# shield-p1000_v53.net
KiCad netlist of a schematic drawn in EAGLE
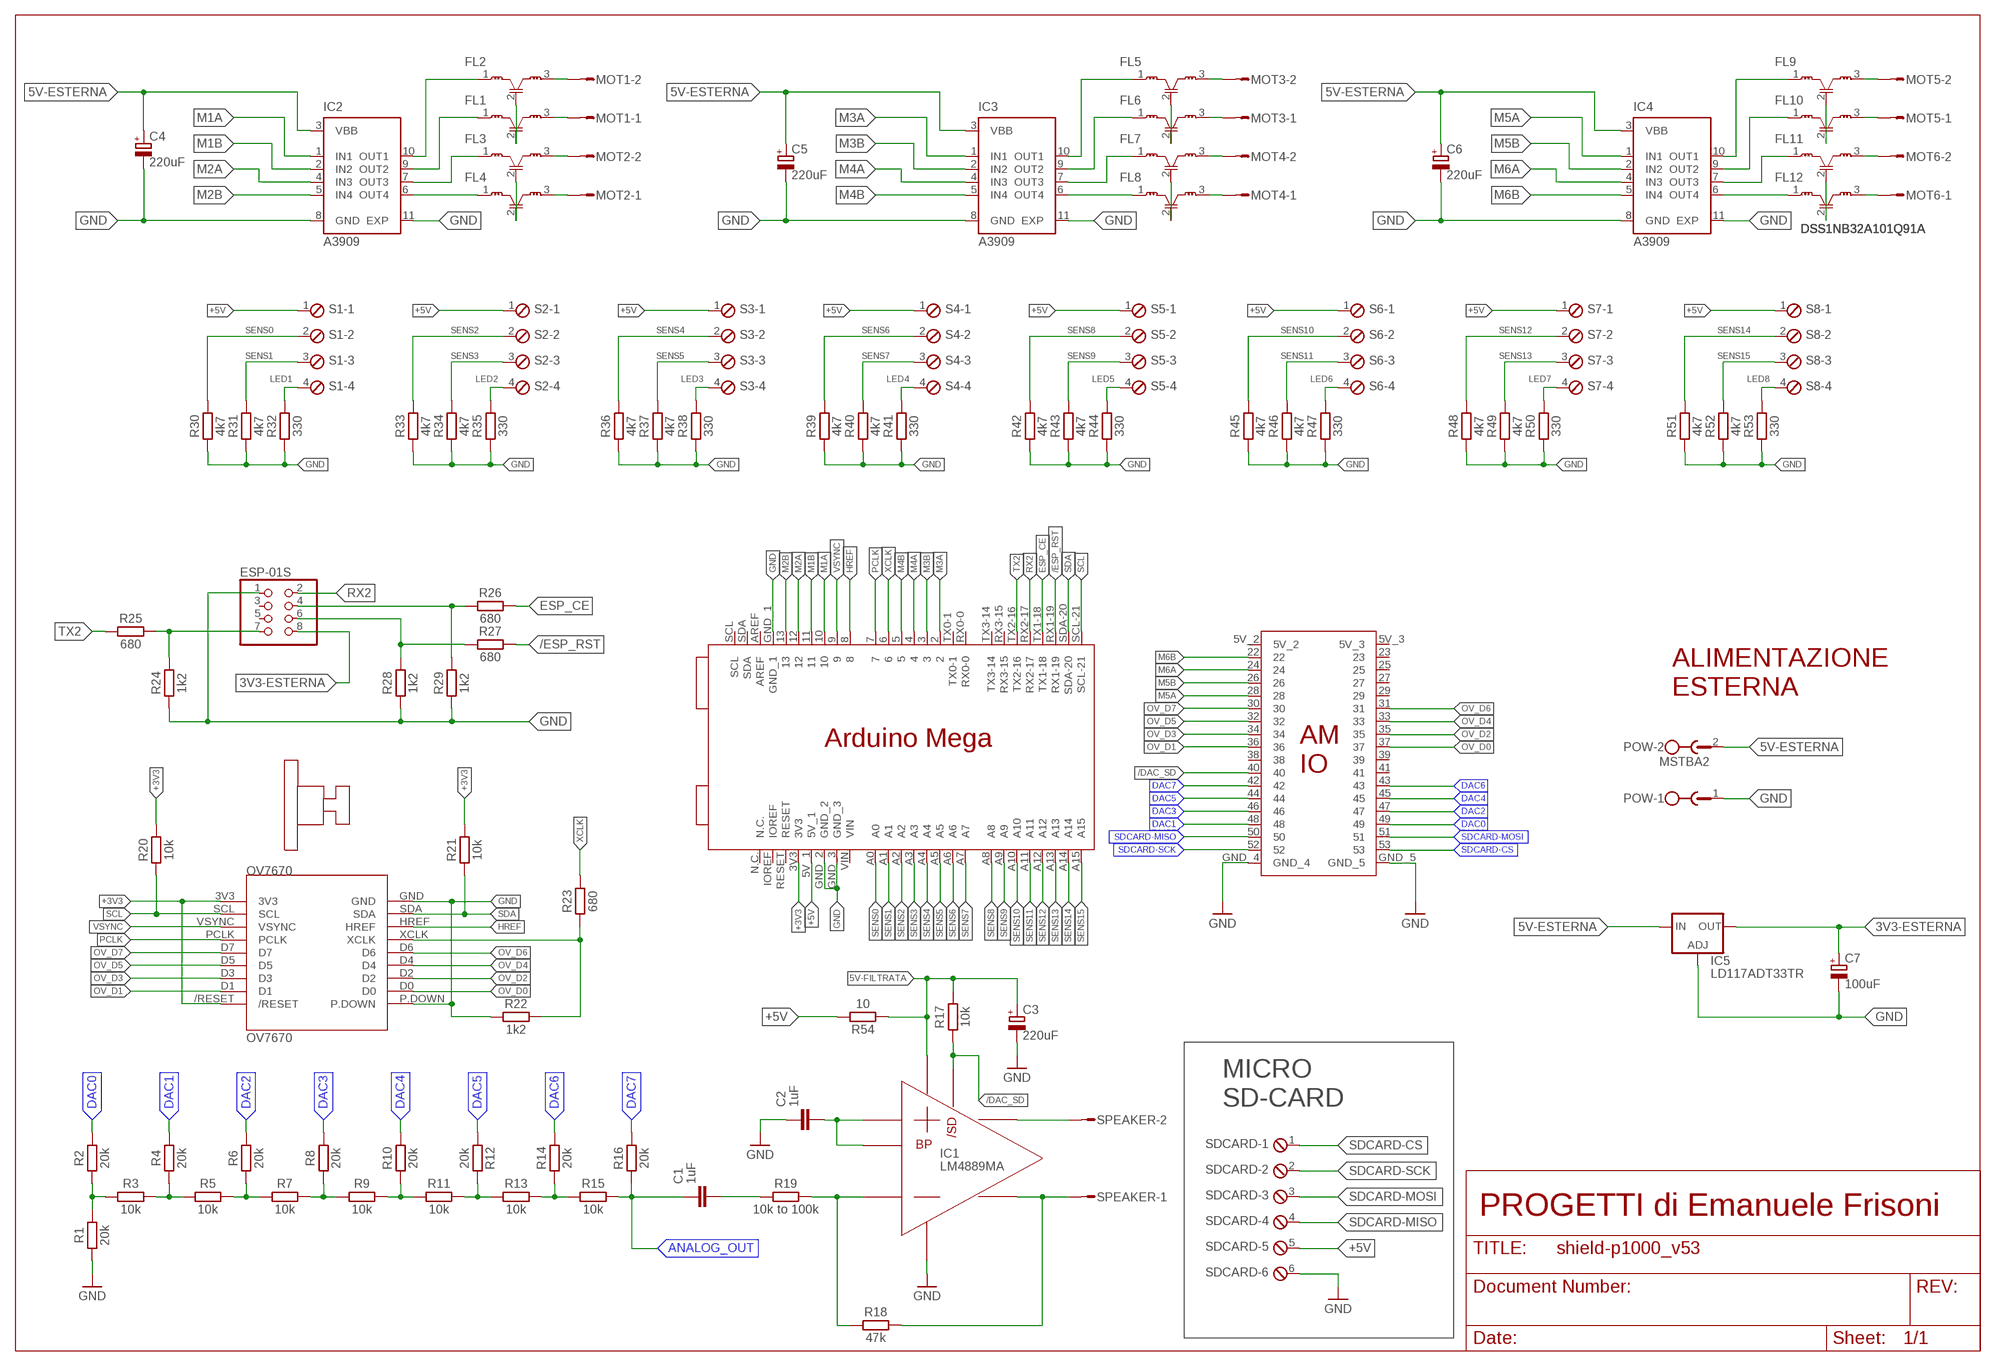
[diagram p0: schematic, sheet 1]

(export (version "E")
  (design (tool "Eeschema 10.0.6"))
  (components
    (comp (ref "ARDUINO-MEGA1")
      (value "ARDUINO-MEGA-SH")
      (footprint "eagle-import:ARDUINO-MEGA-SH")
      (libsource (lib "eagle-import") (part "ARDUINO-MEGA-SH"))
    )
    (comp (ref "C1")
      (value "1uF")
      (footprint "eagle-import:CAPC1608X85")
      (libsource (lib "eagle-import") (part "CCHIP-0603(1608-METRIC)_"))
    )
    (comp (ref "C2")
      (value "1uF")
      (footprint "eagle-import:CAPC1608X85")
      (libsource (lib "eagle-import") (part "CCHIP-0603(1608-METRIC)_"))
    )
    (comp (ref "C3")
      (value "220uF")
      (footprint "eagle-import:E3,5-10")
      (libsource (lib "eagle-import") (part "CPOL-EUE3.5-10"))
    )
    (comp (ref "C4")
      (value "220uF")
      (footprint "eagle-import:E3,5-10")
      (libsource (lib "eagle-import") (part "CPOL-EUE3.5-10"))
    )
    (comp (ref "C5")
      (value "220uF")
      (footprint "eagle-import:E3,5-10")
      (libsource (lib "eagle-import") (part "CPOL-EUE3.5-10"))
    )
    (comp (ref "C6")
      (value "220uF")
      (footprint "eagle-import:E3,5-10")
      (libsource (lib "eagle-import") (part "CPOL-EUE3.5-10"))
    )
    (comp (ref "C7")
      (value "100uF")
      (footprint "eagle-import:E3,5-10")
      (libsource (lib "eagle-import") (part "CPOL-EUE3.5-10"))
    )
    (comp (ref "ESP-01S")
      (value "PINHD-2X4")
      (footprint "eagle-import:2X04")
      (libsource (lib "eagle-import") (part "PINHD-2X4"))
    )
    (comp (ref "FL1")
      (value "DSS1NB32A101Q91A")
      (footprint "eagle-import:RADIAL-3")
      (fields (field (name "MANUFACTURER") "Murata Electronics") (field (name "CREATED_BY") "PCBLayout.com"))
      (libsource (lib "eagle-import") (part "DSS1NB32A101Q91A"))
    )
    (comp (ref "FL2")
      (value "DSS1NB32A101Q91A")
      (footprint "eagle-import:RADIAL-3")
      (fields (field (name "MANUFACTURER") "Murata Electronics") (field (name "CREATED_BY") "PCBLayout.com"))
      (libsource (lib "eagle-import") (part "DSS1NB32A101Q91A"))
    )
    (comp (ref "FL3")
      (value "DSS1NB32A101Q91A")
      (footprint "eagle-import:RADIAL-3")
      (fields (field (name "MANUFACTURER") "Murata Electronics") (field (name "CREATED_BY") "PCBLayout.com"))
      (libsource (lib "eagle-import") (part "DSS1NB32A101Q91A"))
    )
    (comp (ref "FL4")
      (value "DSS1NB32A101Q91A")
      (footprint "eagle-import:RADIAL-3")
      (fields (field (name "MANUFACTURER") "Murata Electronics") (field (name "CREATED_BY") "PCBLayout.com"))
      (libsource (lib "eagle-import") (part "DSS1NB32A101Q91A"))
    )
    (comp (ref "FL5")
      (value "DSS1NB32A101Q91A")
      (footprint "eagle-import:RADIAL-3")
      (fields (field (name "MANUFACTURER") "Murata Electronics") (field (name "CREATED_BY") "PCBLayout.com"))
      (libsource (lib "eagle-import") (part "DSS1NB32A101Q91A"))
    )
    (comp (ref "FL6")
      (value "DSS1NB32A101Q91A")
      (footprint "eagle-import:RADIAL-3")
      (fields (field (name "MANUFACTURER") "Murata Electronics") (field (name "CREATED_BY") "PCBLayout.com"))
      (libsource (lib "eagle-import") (part "DSS1NB32A101Q91A"))
    )
    (comp (ref "FL7")
      (value "DSS1NB32A101Q91A")
      (footprint "eagle-import:RADIAL-3")
      (fields (field (name "MANUFACTURER") "Murata Electronics") (field (name "CREATED_BY") "PCBLayout.com"))
      (libsource (lib "eagle-import") (part "DSS1NB32A101Q91A"))
    )
    (comp (ref "FL8")
      (value "DSS1NB32A101Q91A")
      (footprint "eagle-import:RADIAL-3")
      (fields (field (name "MANUFACTURER") "Murata Electronics") (field (name "CREATED_BY") "PCBLayout.com"))
      (libsource (lib "eagle-import") (part "DSS1NB32A101Q91A"))
    )
    (comp (ref "FL9")
      (value "DSS1NB32A101Q91A")
      (footprint "eagle-import:RADIAL-3")
      (fields (field (name "MANUFACTURER") "Murata Electronics") (field (name "CREATED_BY") "PCBLayout.com"))
      (libsource (lib "eagle-import") (part "DSS1NB32A101Q91A"))
    )
    (comp (ref "FL10")
      (value "DSS1NB32A101Q91A")
      (footprint "eagle-import:RADIAL-3")
      (fields (field (name "MANUFACTURER") "Murata Electronics") (field (name "CREATED_BY") "PCBLayout.com"))
      (libsource (lib "eagle-import") (part "DSS1NB32A101Q91A"))
    )
    (comp (ref "FL11")
      (value "DSS1NB32A101Q91A")
      (footprint "eagle-import:RADIAL-3")
      (fields (field (name "MANUFACTURER") "Murata Electronics") (field (name "CREATED_BY") "PCBLayout.com"))
      (libsource (lib "eagle-import") (part "DSS1NB32A101Q91A"))
    )
    (comp (ref "FL12")
      (value "DSS1NB32A101Q91A")
      (footprint "eagle-import:RADIAL-3")
      (fields (field (name "MANUFACTURER") "Murata Electronics") (field (name "CREATED_BY") "PCBLayout.com"))
      (libsource (lib "eagle-import") (part "DSS1NB32A101Q91A"))
    )
    (comp (ref "IC1")
      (value "LM4889MA")
      (footprint "eagle-import:SOIC127P599X175-8N")
      (libsource (lib "eagle-import") (part "LM4889MA"))
    )
    (comp (ref "IC2")
      (value "A3909")
      (footprint "eagle-import:10-MSOP")
      (libsource (lib "eagle-import") (part "A3909LY"))
    )
    (comp (ref "IC3")
      (value "A3909")
      (footprint "eagle-import:10-MSOP")
      (libsource (lib "eagle-import") (part "A3909LY"))
    )
    (comp (ref "IC4")
      (value "A3909")
      (footprint "eagle-import:10-MSOP")
      (libsource (lib "eagle-import") (part "A3909LY"))
    )
    (comp (ref "IC5")
      (value "LD117ADT33TR")
      (footprint "eagle-import:DPACK")
      (libsource (lib "eagle-import") (part "LD117A?DT33TR"))
    )
    (comp (ref "MOT1")
      (value "S02P")
      (footprint "eagle-import:S02P")
      (libsource (lib "eagle-import") (part "S02P"))
    )
    (comp (ref "MOT2")
      (value "S02P")
      (footprint "eagle-import:S02P")
      (libsource (lib "eagle-import") (part "S02P"))
    )
    (comp (ref "MOT3")
      (value "S02P")
      (footprint "eagle-import:S02P")
      (libsource (lib "eagle-import") (part "S02P"))
    )
    (comp (ref "MOT4")
      (value "S02P")
      (footprint "eagle-import:S02P")
      (libsource (lib "eagle-import") (part "S02P"))
    )
    (comp (ref "MOT5")
      (value "S02P")
      (footprint "eagle-import:S02P")
      (libsource (lib "eagle-import") (part "S02P"))
    )
    (comp (ref "MOT6")
      (value "S02P")
      (footprint "eagle-import:S02P")
      (libsource (lib "eagle-import") (part "S02P"))
    )
    (comp (ref "OV7670")
      (value "OV7670")
      (footprint "eagle-import:OV7670-HEADER")
      (libsource (lib "eagle-import") (part "OV7670"))
    )
    (comp (ref "POW")
      (value "MSTBA2")
      (footprint "eagle-import:MSTBA2")
      (fields (field (name "MF") "FARNELL") (field (name "MPN") "1757242"))
      (libsource (lib "eagle-import") (part "MSTBA2"))
    )
    (comp (ref "R1")
      (value "20k")
      (footprint "eagle-import:RESC1608X60")
      (libsource (lib "eagle-import") (part "RCHIP-0603(1608-METRIC)_"))
    )
    (comp (ref "R2")
      (value "20k")
      (footprint "eagle-import:RESC1608X60")
      (libsource (lib "eagle-import") (part "RCHIP-0603(1608-METRIC)_"))
    )
    (comp (ref "R3")
      (value "10k")
      (footprint "eagle-import:RESC1608X60")
      (libsource (lib "eagle-import") (part "RCHIP-0603(1608-METRIC)_"))
    )
    (comp (ref "R4")
      (value "20k")
      (footprint "eagle-import:RESC1608X60")
      (libsource (lib "eagle-import") (part "RCHIP-0603(1608-METRIC)_"))
    )
    (comp (ref "R5")
      (value "10k")
      (footprint "eagle-import:RESC1608X60")
      (libsource (lib "eagle-import") (part "RCHIP-0603(1608-METRIC)_"))
    )
    (comp (ref "R6")
      (value "20k")
      (footprint "eagle-import:RESC1608X60")
      (libsource (lib "eagle-import") (part "RCHIP-0603(1608-METRIC)_"))
    )
    (comp (ref "R7")
      (value "10k")
      (footprint "eagle-import:RESC1608X60")
      (libsource (lib "eagle-import") (part "RCHIP-0603(1608-METRIC)_"))
    )
    (comp (ref "R8")
      (value "20k")
      (footprint "eagle-import:RESC1608X60")
      (libsource (lib "eagle-import") (part "RCHIP-0603(1608-METRIC)_"))
    )
    (comp (ref "R9")
      (value "10k")
      (footprint "eagle-import:RESC1608X60")
      (libsource (lib "eagle-import") (part "RCHIP-0603(1608-METRIC)_"))
    )
    (comp (ref "R10")
      (value "20k")
      (footprint "eagle-import:RESC1608X60")
      (libsource (lib "eagle-import") (part "RCHIP-0603(1608-METRIC)_"))
    )
    (comp (ref "R11")
      (value "10k")
      (footprint "eagle-import:RESC1608X60")
      (libsource (lib "eagle-import") (part "RCHIP-0603(1608-METRIC)_"))
    )
    (comp (ref "R12")
      (value "20k")
      (footprint "eagle-import:RESC1608X60")
      (libsource (lib "eagle-import") (part "RCHIP-0603(1608-METRIC)_"))
    )
    (comp (ref "R13")
      (value "10k")
      (footprint "eagle-import:RESC1608X60")
      (libsource (lib "eagle-import") (part "RCHIP-0603(1608-METRIC)_"))
    )
    (comp (ref "R14")
      (value "20k")
      (footprint "eagle-import:RESC1608X60")
      (libsource (lib "eagle-import") (part "RCHIP-0603(1608-METRIC)_"))
    )
    (comp (ref "R15")
      (value "10k")
      (footprint "eagle-import:RESC1608X60")
      (libsource (lib "eagle-import") (part "RCHIP-0603(1608-METRIC)_"))
    )
    (comp (ref "R16")
      (value "20k")
      (footprint "eagle-import:RESC1608X60")
      (libsource (lib "eagle-import") (part "RCHIP-0603(1608-METRIC)_"))
    )
    (comp (ref "R17")
      (value "10k")
      (footprint "eagle-import:RESC1608X60")
      (libsource (lib "eagle-import") (part "RCHIP-0603(1608-METRIC)_"))
    )
    (comp (ref "R18")
      (value "47k")
      (footprint "eagle-import:RESC1608X60")
      (libsource (lib "eagle-import") (part "RCHIP-0603(1608-METRIC)_"))
    )
    (comp (ref "R19")
      (value "10k to 100k")
      (footprint "eagle-import:RESAD724W46L381D178B")
      (libsource (lib "eagle-import") (part "RAXIAL-7.2MM-PITCH_"))
    )
    (comp (ref "R20")
      (value "10k")
      (footprint "eagle-import:RESC1608X60")
      (libsource (lib "eagle-import") (part "RCHIP-0603(1608-METRIC)_"))
    )
    (comp (ref "R21")
      (value "10k")
      (footprint "eagle-import:RESC1608X60")
      (libsource (lib "eagle-import") (part "RCHIP-0603(1608-METRIC)_"))
    )
    (comp (ref "R22")
      (value "1k2")
      (footprint "eagle-import:RESC1608X60")
      (libsource (lib "eagle-import") (part "RCHIP-0603(1608-METRIC)_"))
    )
    (comp (ref "R23")
      (value "680")
      (footprint "eagle-import:RESC1608X60")
      (libsource (lib "eagle-import") (part "RCHIP-0603(1608-METRIC)_"))
    )
    (comp (ref "R24")
      (value "1k2")
      (footprint "eagle-import:RESC1608X60")
      (libsource (lib "eagle-import") (part "RCHIP-0603(1608-METRIC)_"))
    )
    (comp (ref "R25")
      (value "680")
      (footprint "eagle-import:RESC1608X60")
      (libsource (lib "eagle-import") (part "RCHIP-0603(1608-METRIC)_"))
    )
    (comp (ref "R26")
      (value "680")
      (footprint "eagle-import:RESC1608X60")
      (libsource (lib "eagle-import") (part "RCHIP-0603(1608-METRIC)_"))
    )
    (comp (ref "R27")
      (value "680")
      (footprint "eagle-import:RESC1608X60")
      (libsource (lib "eagle-import") (part "RCHIP-0603(1608-METRIC)_"))
    )
    (comp (ref "R28")
      (value "1k2")
      (footprint "eagle-import:RESC1608X60")
      (libsource (lib "eagle-import") (part "RCHIP-0603(1608-METRIC)_"))
    )
    (comp (ref "R29")
      (value "1k2")
      (footprint "eagle-import:RESC1608X60")
      (libsource (lib "eagle-import") (part "RCHIP-0603(1608-METRIC)_"))
    )
    (comp (ref "R30")
      (value "4k7")
      (footprint "eagle-import:RESC1608X60")
      (libsource (lib "eagle-import") (part "RCHIP-0603(1608-METRIC)_"))
    )
    (comp (ref "R31")
      (value "4k7")
      (footprint "eagle-import:RESC1608X60")
      (libsource (lib "eagle-import") (part "RCHIP-0603(1608-METRIC)_"))
    )
    (comp (ref "R32")
      (value "330")
      (footprint "eagle-import:RESC1608X60")
      (libsource (lib "eagle-import") (part "RCHIP-0603(1608-METRIC)_"))
    )
    (comp (ref "R33")
      (value "4k7")
      (footprint "eagle-import:RESC1608X60")
      (libsource (lib "eagle-import") (part "RCHIP-0603(1608-METRIC)_"))
    )
    (comp (ref "R34")
      (value "4k7")
      (footprint "eagle-import:RESC1608X60")
      (libsource (lib "eagle-import") (part "RCHIP-0603(1608-METRIC)_"))
    )
    (comp (ref "R35")
      (value "330")
      (footprint "eagle-import:RESC1608X60")
      (libsource (lib "eagle-import") (part "RCHIP-0603(1608-METRIC)_"))
    )
    (comp (ref "R36")
      (value "4k7")
      (footprint "eagle-import:RESC1608X60")
      (libsource (lib "eagle-import") (part "RCHIP-0603(1608-METRIC)_"))
    )
    (comp (ref "R37")
      (value "4k7")
      (footprint "eagle-import:RESC1608X60")
      (libsource (lib "eagle-import") (part "RCHIP-0603(1608-METRIC)_"))
    )
    (comp (ref "R38")
      (value "330")
      (footprint "eagle-import:RESC1608X60")
      (libsource (lib "eagle-import") (part "RCHIP-0603(1608-METRIC)_"))
    )
    (comp (ref "R39")
      (value "4k7")
      (footprint "eagle-import:RESC1608X60")
      (libsource (lib "eagle-import") (part "RCHIP-0603(1608-METRIC)_"))
    )
    (comp (ref "R40")
      (value "4k7")
      (footprint "eagle-import:RESC1608X60")
      (libsource (lib "eagle-import") (part "RCHIP-0603(1608-METRIC)_"))
    )
    (comp (ref "R41")
      (value "330")
      (footprint "eagle-import:RESC1608X60")
      (libsource (lib "eagle-import") (part "RCHIP-0603(1608-METRIC)_"))
    )
    (comp (ref "R42")
      (value "4k7")
      (footprint "eagle-import:RESC1608X60")
      (libsource (lib "eagle-import") (part "RCHIP-0603(1608-METRIC)_"))
    )
    (comp (ref "R43")
      (value "4k7")
      (footprint "eagle-import:RESC1608X60")
      (libsource (lib "eagle-import") (part "RCHIP-0603(1608-METRIC)_"))
    )
    (comp (ref "R44")
      (value "330")
      (footprint "eagle-import:RESC1608X60")
      (libsource (lib "eagle-import") (part "RCHIP-0603(1608-METRIC)_"))
    )
    (comp (ref "R45")
      (value "4k7")
      (footprint "eagle-import:RESC1608X60")
      (libsource (lib "eagle-import") (part "RCHIP-0603(1608-METRIC)_"))
    )
    (comp (ref "R46")
      (value "4k7")
      (footprint "eagle-import:RESC1608X60")
      (libsource (lib "eagle-import") (part "RCHIP-0603(1608-METRIC)_"))
    )
    (comp (ref "R47")
      (value "330")
      (footprint "eagle-import:RESC1608X60")
      (libsource (lib "eagle-import") (part "RCHIP-0603(1608-METRIC)_"))
    )
    (comp (ref "R48")
      (value "4k7")
      (footprint "eagle-import:RESC1608X60")
      (libsource (lib "eagle-import") (part "RCHIP-0603(1608-METRIC)_"))
    )
    (comp (ref "R49")
      (value "4k7")
      (footprint "eagle-import:RESC1608X60")
      (libsource (lib "eagle-import") (part "RCHIP-0603(1608-METRIC)_"))
    )
    (comp (ref "R50")
      (value "330")
      (footprint "eagle-import:RESC1608X60")
      (libsource (lib "eagle-import") (part "RCHIP-0603(1608-METRIC)_"))
    )
    (comp (ref "R51")
      (value "4k7")
      (footprint "eagle-import:RESC1608X60")
      (libsource (lib "eagle-import") (part "RCHIP-0603(1608-METRIC)_"))
    )
    (comp (ref "R52")
      (value "4k7")
      (footprint "eagle-import:RESC1608X60")
      (libsource (lib "eagle-import") (part "RCHIP-0603(1608-METRIC)_"))
    )
    (comp (ref "R53")
      (value "330")
      (footprint "eagle-import:RESC1608X60")
      (libsource (lib "eagle-import") (part "RCHIP-0603(1608-METRIC)_"))
    )
    (comp (ref "R54")
      (value "10")
      (footprint "eagle-import:RESC1608X60")
      (libsource (lib "eagle-import") (part "RCHIP-0603(1608-METRIC)_"))
    )
    (comp (ref "S1")
      (value "MPT4")
      (footprint "eagle-import:4POL254")
      (libsource (lib "eagle-import") (part "MPT4"))
    )
    (comp (ref "S2")
      (value "MPT4")
      (footprint "eagle-import:4POL254")
      (libsource (lib "eagle-import") (part "MPT4"))
    )
    (comp (ref "S3")
      (value "MPT4")
      (footprint "eagle-import:4POL254")
      (libsource (lib "eagle-import") (part "MPT4"))
    )
    (comp (ref "S4")
      (value "MPT4")
      (footprint "eagle-import:4POL254")
      (libsource (lib "eagle-import") (part "MPT4"))
    )
    (comp (ref "S5")
      (value "MPT4")
      (footprint "eagle-import:4POL254")
      (libsource (lib "eagle-import") (part "MPT4"))
    )
    (comp (ref "S6")
      (value "MPT4")
      (footprint "eagle-import:4POL254")
      (libsource (lib "eagle-import") (part "MPT4"))
    )
    (comp (ref "S7")
      (value "MPT4")
      (footprint "eagle-import:4POL254")
      (libsource (lib "eagle-import") (part "MPT4"))
    )
    (comp (ref "S8")
      (value "MPT4")
      (footprint "eagle-import:4POL254")
      (libsource (lib "eagle-import") (part "MPT4"))
    )
    (comp (ref "SDCARD")
      (value "MPT6")
      (footprint "eagle-import:6POL254")
      (libsource (lib "eagle-import") (part "MPT6"))
    )
    (comp (ref "SPEAKER")
      (value "S02P")
      (footprint "eagle-import:S02P")
      (libsource (lib "eagle-import") (part "S02P"))
    )
  )
  (nets
    (net (code "1") (name "+3V3") (class "Default")
      (node (ref "ARDUINO-MEGA1") (pin "3V3") (pinfunction "3V3_3V3") (pintype "bidirectional"))
      (node (ref "OV7670") (pin "/RESET") (pinfunction "/RESET_/RESET") (pintype "bidirectional"))
      (node (ref "OV7670") (pin "3V3") (pinfunction "3V3_3V3") (pintype "bidirectional"))
      (node (ref "R20") (pin "2") (pinfunction "2_2") (pintype "passive"))
      (node (ref "R21") (pin "2") (pinfunction "2_2") (pintype "passive"))
    )
    (net (code "2") (name "+5V") (class "Default")
      (node (ref "ARDUINO-MEGA1") (pin "5V_1") (pinfunction "5V_1_5V_1") (pintype "bidirectional"))
      (node (ref "R54") (pin "1") (pinfunction "1_1") (pintype "passive"))
      (node (ref "S1") (pin "1") (pinfunction "1_1") (pintype "passive"))
      (node (ref "S2") (pin "1") (pinfunction "1_1") (pintype "passive"))
      (node (ref "S3") (pin "1") (pinfunction "1_1") (pintype "passive"))
      (node (ref "S4") (pin "1") (pinfunction "1_1") (pintype "passive"))
      (node (ref "S5") (pin "1") (pinfunction "1_1") (pintype "passive"))
      (node (ref "S6") (pin "1") (pinfunction "1_1") (pintype "passive"))
      (node (ref "S7") (pin "1") (pinfunction "1_1") (pintype "passive"))
      (node (ref "S8") (pin "1") (pinfunction "1_1") (pintype "passive"))
      (node (ref "SDCARD") (pin "5") (pinfunction "1_5") (pintype "passive"))
    )
    (net (code "3") (name "/LED1") (class "Default")
      (node (ref "R32") (pin "2") (pinfunction "2_2") (pintype "passive"))
      (node (ref "S1") (pin "4") (pinfunction "1_4") (pintype "passive"))
    )
    (net (code "4") (name "/LED2") (class "Default")
      (node (ref "R35") (pin "2") (pinfunction "2_2") (pintype "passive"))
      (node (ref "S2") (pin "4") (pinfunction "1_4") (pintype "passive"))
    )
    (net (code "5") (name "/LED3") (class "Default")
      (node (ref "R38") (pin "2") (pinfunction "2_2") (pintype "passive"))
      (node (ref "S3") (pin "4") (pinfunction "1_4") (pintype "passive"))
    )
    (net (code "6") (name "/LED4") (class "Default")
      (node (ref "R41") (pin "2") (pinfunction "2_2") (pintype "passive"))
      (node (ref "S4") (pin "4") (pinfunction "1_4") (pintype "passive"))
    )
    (net (code "7") (name "/LED5") (class "Default")
      (node (ref "R44") (pin "2") (pinfunction "2_2") (pintype "passive"))
      (node (ref "S5") (pin "4") (pinfunction "1_4") (pintype "passive"))
    )
    (net (code "8") (name "/LED6") (class "Default")
      (node (ref "R47") (pin "2") (pinfunction "2_2") (pintype "passive"))
      (node (ref "S6") (pin "4") (pinfunction "1_4") (pintype "passive"))
    )
    (net (code "9") (name "/LED7") (class "Default")
      (node (ref "R50") (pin "2") (pinfunction "2_2") (pintype "passive"))
      (node (ref "S7") (pin "4") (pinfunction "1_4") (pintype "passive"))
    )
    (net (code "10") (name "/LED8") (class "Default")
      (node (ref "R53") (pin "2") (pinfunction "2_2") (pintype "passive"))
      (node (ref "S8") (pin "4") (pinfunction "1_4") (pintype "passive"))
    )
    (net (code "11") (name "3V3-ESTERNA") (class "Default")
      (node (ref "C7") (pin "+") (pinfunction "+_+") (pintype "passive"))
      (node (ref "ESP-01S") (pin "8") (pinfunction "8_8") (pintype "passive"))
      (node (ref "IC5") (pin "4") (pinfunction "OUT_4") (pintype "passive"))
    )
    (net (code "12") (name "5V-ESTERNA") (class "Default")
      (node (ref "C4") (pin "+") (pinfunction "+_+") (pintype "passive"))
      (node (ref "C5") (pin "+") (pinfunction "+_+") (pintype "passive"))
      (node (ref "C6") (pin "+") (pinfunction "+_+") (pintype "passive"))
      (node (ref "IC2") (pin "3") (pinfunction "VBB_3") (pintype "power_in"))
      (node (ref "IC3") (pin "3") (pinfunction "VBB_3") (pintype "power_in"))
      (node (ref "IC4") (pin "3") (pinfunction "VBB_3") (pintype "power_in"))
      (node (ref "IC5") (pin "3") (pinfunction "IN_3") (pintype "input"))
      (node (ref "POW") (pin "2") (pinfunction "1_2") (pintype "passive"))
    )
    (net (code "13") (name "5V-FILTRATA") (class "Default")
      (node (ref "C3") (pin "+") (pinfunction "+_+") (pintype "passive"))
      (node (ref "IC1") (pin "6") (pinfunction "VDD_6") (pintype "bidirectional"))
      (node (ref "R17") (pin "1") (pinfunction "1_1") (pintype "passive"))
      (node (ref "R54") (pin "2") (pinfunction "2_2") (pintype "passive"))
    )
    (net (code "14") (name "ANALOG_OUT") (class "Default")
      (node (ref "C1") (pin "1") (pinfunction "1_1") (pintype "passive"))
      (node (ref "R15") (pin "1") (pinfunction "1_1") (pintype "passive"))
      (node (ref "R16") (pin "2") (pinfunction "2_2") (pintype "passive"))
    )
    (net (code "15") (name "DAC0") (class "Default")
      (node (ref "ARDUINO-MEGA1") (pin "49") (pinfunction "49_49") (pintype "bidirectional"))
      (node (ref "R2") (pin "1") (pinfunction "1_1") (pintype "passive"))
    )
    (net (code "16") (name "DAC1") (class "Default")
      (node (ref "ARDUINO-MEGA1") (pin "48") (pinfunction "48_48") (pintype "bidirectional"))
      (node (ref "R4") (pin "1") (pinfunction "1_1") (pintype "passive"))
    )
    (net (code "17") (name "DAC2") (class "Default")
      (node (ref "ARDUINO-MEGA1") (pin "47") (pinfunction "47_47") (pintype "bidirectional"))
      (node (ref "R6") (pin "1") (pinfunction "1_1") (pintype "passive"))
    )
    (net (code "18") (name "DAC3") (class "Default")
      (node (ref "ARDUINO-MEGA1") (pin "46") (pinfunction "46_46") (pintype "bidirectional"))
      (node (ref "R8") (pin "1") (pinfunction "1_1") (pintype "passive"))
    )
    (net (code "19") (name "DAC4") (class "Default")
      (node (ref "ARDUINO-MEGA1") (pin "45") (pinfunction "45_45") (pintype "bidirectional"))
      (node (ref "R10") (pin "1") (pinfunction "1_1") (pintype "passive"))
    )
    (net (code "20") (name "DAC5") (class "Default")
      (node (ref "ARDUINO-MEGA1") (pin "44") (pinfunction "44_44") (pintype "bidirectional"))
      (node (ref "R12") (pin "1") (pinfunction "1_1") (pintype "passive"))
    )
    (net (code "21") (name "DAC6") (class "Default")
      (node (ref "ARDUINO-MEGA1") (pin "43") (pinfunction "43_43") (pintype "bidirectional"))
      (node (ref "R14") (pin "1") (pinfunction "1_1") (pintype "passive"))
    )
    (net (code "22") (name "DAC7") (class "Default")
      (node (ref "ARDUINO-MEGA1") (pin "42") (pinfunction "42_42") (pintype "bidirectional"))
      (node (ref "R16") (pin "1") (pinfunction "1_1") (pintype "passive"))
    )
    (net (code "23") (name "ESP_CE") (class "Default")
      (node (ref "ARDUINO-MEGA1") (pin "TX1-18") (pinfunction "TX1-18_TX1-18") (pintype "bidirectional"))
      (node (ref "R26") (pin "2") (pinfunction "2_2") (pintype "passive"))
    )
    (net (code "24") (name "GND") (class "Default")
      (node (ref "ARDUINO-MEGA1") (pin "GND_1") (pinfunction "GND_1_GND_1") (pintype "bidirectional"))
      (node (ref "ARDUINO-MEGA1") (pin "GND_2") (pinfunction "GND_2_GND_2") (pintype "bidirectional"))
      (node (ref "ARDUINO-MEGA1") (pin "GND_3") (pinfunction "GND_3_GND_3") (pintype "bidirectional"))
      (node (ref "ARDUINO-MEGA1") (pin "GND_4") (pinfunction "GND_4_GND_4") (pintype "bidirectional"))
      (node (ref "ARDUINO-MEGA1") (pin "GND_5") (pinfunction "GND_5_GND_5") (pintype "bidirectional"))
      (node (ref "C2") (pin "1") (pinfunction "1_1") (pintype "passive"))
      (node (ref "C3") (pin "-") (pinfunction "-_-") (pintype "passive"))
      (node (ref "C4") (pin "-") (pinfunction "-_-") (pintype "passive"))
      (node (ref "C5") (pin "-") (pinfunction "-_-") (pintype "passive"))
      (node (ref "C6") (pin "-") (pinfunction "-_-") (pintype "passive"))
      (node (ref "C7") (pin "-") (pinfunction "-_-") (pintype "passive"))
      (node (ref "ESP-01S") (pin "1") (pinfunction "1_1") (pintype "passive"))
      (node (ref "IC1") (pin "7") (pinfunction "VSS_7") (pintype "bidirectional"))
      (node (ref "IC2") (pin "11") (pinfunction "EXP_11") (pintype "passive"))
      (node (ref "IC2") (pin "8") (pinfunction "GND_8") (pintype "power_in"))
      (node (ref "IC3") (pin "11") (pinfunction "EXP_11") (pintype "passive"))
      (node (ref "IC3") (pin "8") (pinfunction "GND_8") (pintype "power_in"))
      (node (ref "IC4") (pin "11") (pinfunction "EXP_11") (pintype "passive"))
      (node (ref "IC4") (pin "8") (pinfunction "GND_8") (pintype "power_in"))
      (node (ref "IC5") (pin "1") (pinfunction "ADJ_1") (pintype "input"))
      (node (ref "OV7670") (pin "GND") (pinfunction "GND_GND") (pintype "bidirectional"))
      (node (ref "OV7670") (pin "P.DOWN") (pinfunction "P.DOWN_P.DOWN") (pintype "bidirectional"))
      (node (ref "POW") (pin "1") (pinfunction "1_1") (pintype "passive"))
      (node (ref "R1") (pin "1") (pinfunction "1_1") (pintype "passive"))
      (node (ref "R22") (pin "1") (pinfunction "1_1") (pintype "passive"))
      (node (ref "R24") (pin "1") (pinfunction "1_1") (pintype "passive"))
      (node (ref "R28") (pin "1") (pinfunction "1_1") (pintype "passive"))
      (node (ref "R29") (pin "1") (pinfunction "1_1") (pintype "passive"))
      (node (ref "R30") (pin "1") (pinfunction "1_1") (pintype "passive"))
      (node (ref "R31") (pin "1") (pinfunction "1_1") (pintype "passive"))
      (node (ref "R32") (pin "1") (pinfunction "1_1") (pintype "passive"))
      (node (ref "R33") (pin "1") (pinfunction "1_1") (pintype "passive"))
      (node (ref "R34") (pin "1") (pinfunction "1_1") (pintype "passive"))
      (node (ref "R35") (pin "1") (pinfunction "1_1") (pintype "passive"))
      (node (ref "R36") (pin "1") (pinfunction "1_1") (pintype "passive"))
      (node (ref "R37") (pin "1") (pinfunction "1_1") (pintype "passive"))
      (node (ref "R38") (pin "1") (pinfunction "1_1") (pintype "passive"))
      (node (ref "R39") (pin "1") (pinfunction "1_1") (pintype "passive"))
      (node (ref "R40") (pin "1") (pinfunction "1_1") (pintype "passive"))
      (node (ref "R41") (pin "1") (pinfunction "1_1") (pintype "passive"))
      (node (ref "R42") (pin "1") (pinfunction "1_1") (pintype "passive"))
      (node (ref "R43") (pin "1") (pinfunction "1_1") (pintype "passive"))
      (node (ref "R44") (pin "1") (pinfunction "1_1") (pintype "passive"))
      (node (ref "R45") (pin "1") (pinfunction "1_1") (pintype "passive"))
      (node (ref "R46") (pin "1") (pinfunction "1_1") (pintype "passive"))
      (node (ref "R47") (pin "1") (pinfunction "1_1") (pintype "passive"))
      (node (ref "R48") (pin "1") (pinfunction "1_1") (pintype "passive"))
      (node (ref "R49") (pin "1") (pinfunction "1_1") (pintype "passive"))
      (node (ref "R50") (pin "1") (pinfunction "1_1") (pintype "passive"))
      (node (ref "R51") (pin "1") (pinfunction "1_1") (pintype "passive"))
      (node (ref "R52") (pin "1") (pinfunction "1_1") (pintype "passive"))
      (node (ref "R53") (pin "1") (pinfunction "1_1") (pintype "passive"))
      (node (ref "SDCARD") (pin "6") (pinfunction "1_6") (pintype "passive"))
    )
    (net (code "25") (name "HREF") (class "Default")
      (node (ref "ARDUINO-MEGA1") (pin "8") (pinfunction "8_8") (pintype "bidirectional"))
      (node (ref "OV7670") (pin "HREF") (pinfunction "HREF_HREF") (pintype "bidirectional"))
    )
    (net (code "26") (name "M1A") (class "Default")
      (node (ref "ARDUINO-MEGA1") (pin "10") (pinfunction "10_10") (pintype "bidirectional"))
      (node (ref "IC2") (pin "1") (pinfunction "IN1_1") (pintype "input"))
    )
    (net (code "27") (name "M1B") (class "Default")
      (node (ref "ARDUINO-MEGA1") (pin "11") (pinfunction "11_11") (pintype "bidirectional"))
      (node (ref "IC2") (pin "2") (pinfunction "IN2_2") (pintype "input"))
    )
    (net (code "28") (name "M2A") (class "Default")
      (node (ref "ARDUINO-MEGA1") (pin "12") (pinfunction "12_12") (pintype "bidirectional"))
      (node (ref "IC2") (pin "4") (pinfunction "IN3_4") (pintype "input"))
    )
    (net (code "29") (name "M2B") (class "Default")
      (node (ref "ARDUINO-MEGA1") (pin "13") (pinfunction "13_13") (pintype "bidirectional"))
      (node (ref "IC2") (pin "5") (pinfunction "IN4_5") (pintype "input"))
    )
    (net (code "30") (name "M3A") (class "Default")
      (node (ref "ARDUINO-MEGA1") (pin "2") (pinfunction "2_2") (pintype "bidirectional"))
      (node (ref "IC3") (pin "1") (pinfunction "IN1_1") (pintype "input"))
    )
    (net (code "31") (name "M3B") (class "Default")
      (node (ref "ARDUINO-MEGA1") (pin "3") (pinfunction "3_3") (pintype "bidirectional"))
      (node (ref "IC3") (pin "2") (pinfunction "IN2_2") (pintype "input"))
    )
    (net (code "32") (name "M4A") (class "Default")
      (node (ref "ARDUINO-MEGA1") (pin "4") (pinfunction "4_4") (pintype "bidirectional"))
      (node (ref "IC3") (pin "4") (pinfunction "IN3_4") (pintype "input"))
    )
    (net (code "33") (name "M4B") (class "Default")
      (node (ref "ARDUINO-MEGA1") (pin "5") (pinfunction "5_5") (pintype "bidirectional"))
      (node (ref "IC3") (pin "5") (pinfunction "IN4_5") (pintype "input"))
    )
    (net (code "34") (name "M5A") (class "Default")
      (node (ref "ARDUINO-MEGA1") (pin "28") (pinfunction "28_28") (pintype "bidirectional"))
      (node (ref "IC4") (pin "1") (pinfunction "IN1_1") (pintype "input"))
    )
    (net (code "35") (name "M5B") (class "Default")
      (node (ref "ARDUINO-MEGA1") (pin "26") (pinfunction "26_26") (pintype "bidirectional"))
      (node (ref "IC4") (pin "2") (pinfunction "IN2_2") (pintype "input"))
    )
    (net (code "36") (name "M6A") (class "Default")
      (node (ref "ARDUINO-MEGA1") (pin "24") (pinfunction "24_24") (pintype "bidirectional"))
      (node (ref "IC4") (pin "4") (pinfunction "IN3_4") (pintype "input"))
    )
    (net (code "37") (name "M6B") (class "Default")
      (node (ref "ARDUINO-MEGA1") (pin "22") (pinfunction "22_22") (pintype "bidirectional"))
      (node (ref "IC4") (pin "5") (pinfunction "IN4_5") (pintype "input"))
    )
    (net (code "38") (name "Net-(C1-Pad2)") (class "Default")
      (node (ref "C1") (pin "2") (pinfunction "2_2") (pintype "passive"))
      (node (ref "R19") (pin "1") (pinfunction "1_1") (pintype "passive"))
    )
    (net (code "39") (name "Net-(ESP-01S-Pad4)") (class "Default")
      (node (ref "ESP-01S") (pin "4") (pinfunction "4_4") (pintype "passive"))
      (node (ref "R26") (pin "1") (pinfunction "1_1") (pintype "passive"))
      (node (ref "R29") (pin "2") (pinfunction "2_2") (pintype "passive"))
    )
    (net (code "40") (name "Net-(ESP-01S-Pad6)") (class "Default")
      (node (ref "ESP-01S") (pin "6") (pinfunction "6_6") (pintype "passive"))
      (node (ref "R27") (pin "1") (pinfunction "1_1") (pintype "passive"))
      (node (ref "R28") (pin "2") (pinfunction "2_2") (pintype "passive"))
    )
    (net (code "41") (name "Net-(ESP-01S-Pad7)") (class "Default")
      (node (ref "ESP-01S") (pin "7") (pinfunction "7_7") (pintype "passive"))
      (node (ref "R24") (pin "2") (pinfunction "2_2") (pintype "passive"))
      (node (ref "R25") (pin "2") (pinfunction "2_2") (pintype "passive"))
    )
    (net (code "42") (name "Net-(FL1-GND)") (class "Default")
      (node (ref "FL1") (pin "2") (pinfunction "GND_2") (pintype "passive"))
      (node (ref "FL2") (pin "2") (pinfunction "GND_2") (pintype "passive"))
    )
    (net (code "43") (name "Net-(FL3-GND)") (class "Default")
      (node (ref "FL3") (pin "2") (pinfunction "GND_2") (pintype "passive"))
      (node (ref "FL4") (pin "2") (pinfunction "GND_2") (pintype "passive"))
    )
    (net (code "44") (name "Net-(FL5-GND)") (class "Default")
      (node (ref "FL5") (pin "2") (pinfunction "GND_2") (pintype "passive"))
      (node (ref "FL6") (pin "2") (pinfunction "GND_2") (pintype "passive"))
    )
    (net (code "45") (name "Net-(FL7-GND)") (class "Default")
      (node (ref "FL7") (pin "2") (pinfunction "GND_2") (pintype "passive"))
      (node (ref "FL8") (pin "2") (pinfunction "GND_2") (pintype "passive"))
    )
    (net (code "46") (name "Net-(FL10-GND)") (class "Default")
      (node (ref "FL10") (pin "2") (pinfunction "GND_2") (pintype "passive"))
      (node (ref "FL9") (pin "2") (pinfunction "GND_2") (pintype "passive"))
    )
    (net (code "47") (name "Net-(FL11-GND)") (class "Default")
      (node (ref "FL11") (pin "2") (pinfunction "GND_2") (pintype "passive"))
      (node (ref "FL12") (pin "2") (pinfunction "GND_2") (pintype "passive"))
    )
    (net (code "48") (name "Net-(IC1-BYPASS)") (class "Default")
      (node (ref "C2") (pin "2") (pinfunction "2_2") (pintype "passive"))
      (node (ref "IC1") (pin "2") (pinfunction "BYPASS_2") (pintype "bidirectional"))
      (node (ref "IC1") (pin "3") (pinfunction "IN+_3") (pintype "bidirectional"))
    )
    (net (code "49") (name "Net-(IC1-IN-)") (class "Default")
      (node (ref "IC1") (pin "4") (pinfunction "IN-_4") (pintype "bidirectional"))
      (node (ref "R18") (pin "2") (pinfunction "2_2") (pintype "passive"))
      (node (ref "R19") (pin "2") (pinfunction "2_2") (pintype "passive"))
    )
    (net (code "50") (name "Net-(IC1-VO1)") (class "Default")
      (node (ref "IC1") (pin "5") (pinfunction "VO1_5") (pintype "bidirectional"))
      (node (ref "R18") (pin "1") (pinfunction "1_1") (pintype "passive"))
      (node (ref "SPEAKER") (pin "1") (pinfunction "S_1") (pintype "passive"))
    )
    (net (code "51") (name "Net-(IC1-VO2)") (class "Default")
      (node (ref "IC1") (pin "8") (pinfunction "VO2_8") (pintype "bidirectional"))
      (node (ref "SPEAKER") (pin "2") (pinfunction "S_2") (pintype "passive"))
    )
    (net (code "52") (name "Net-(IC2-OUT1)") (class "Default")
      (node (ref "FL2") (pin "1") (pinfunction "1_1") (pintype "passive"))
      (node (ref "IC2") (pin "10") (pinfunction "OUT1_10") (pintype "output"))
    )
    (net (code "53") (name "Net-(IC2-OUT2)") (class "Default")
      (node (ref "FL1") (pin "1") (pinfunction "1_1") (pintype "passive"))
      (node (ref "IC2") (pin "9") (pinfunction "OUT2_9") (pintype "output"))
    )
    (net (code "54") (name "Net-(IC2-OUT3)") (class "Default")
      (node (ref "FL3") (pin "1") (pinfunction "1_1") (pintype "passive"))
      (node (ref "IC2") (pin "7") (pinfunction "OUT3_7") (pintype "output"))
    )
    (net (code "55") (name "Net-(IC2-OUT4)") (class "Default")
      (node (ref "FL4") (pin "1") (pinfunction "1_1") (pintype "passive"))
      (node (ref "IC2") (pin "6") (pinfunction "OUT4_6") (pintype "output"))
    )
    (net (code "56") (name "Net-(IC3-OUT1)") (class "Default")
      (node (ref "FL5") (pin "1") (pinfunction "1_1") (pintype "passive"))
      (node (ref "IC3") (pin "10") (pinfunction "OUT1_10") (pintype "output"))
    )
    (net (code "57") (name "Net-(IC3-OUT2)") (class "Default")
      (node (ref "FL6") (pin "1") (pinfunction "1_1") (pintype "passive"))
      (node (ref "IC3") (pin "9") (pinfunction "OUT2_9") (pintype "output"))
    )
    (net (code "58") (name "Net-(IC3-OUT3)") (class "Default")
      (node (ref "FL7") (pin "1") (pinfunction "1_1") (pintype "passive"))
      (node (ref "IC3") (pin "7") (pinfunction "OUT3_7") (pintype "output"))
    )
    (net (code "59") (name "Net-(IC3-OUT4)") (class "Default")
      (node (ref "FL8") (pin "1") (pinfunction "1_1") (pintype "passive"))
      (node (ref "IC3") (pin "6") (pinfunction "OUT4_6") (pintype "output"))
    )
    (net (code "60") (name "Net-(IC4-OUT1)") (class "Default")
      (node (ref "FL9") (pin "1") (pinfunction "1_1") (pintype "passive"))
      (node (ref "IC4") (pin "10") (pinfunction "OUT1_10") (pintype "output"))
    )
    (net (code "61") (name "Net-(IC4-OUT2)") (class "Default")
      (node (ref "FL10") (pin "1") (pinfunction "1_1") (pintype "passive"))
      (node (ref "IC4") (pin "9") (pinfunction "OUT2_9") (pintype "output"))
    )
    (net (code "62") (name "Net-(IC4-OUT3)") (class "Default")
      (node (ref "FL11") (pin "1") (pinfunction "1_1") (pintype "passive"))
      (node (ref "IC4") (pin "7") (pinfunction "OUT3_7") (pintype "output"))
    )
    (net (code "63") (name "Net-(IC4-OUT4)") (class "Default")
      (node (ref "FL12") (pin "1") (pinfunction "1_1") (pintype "passive"))
      (node (ref "IC4") (pin "6") (pinfunction "OUT4_6") (pintype "output"))
    )
    (net (code "64") (name "Net-(MOT1A-S)") (class "Default")
      (node (ref "FL1") (pin "3") (pinfunction "3_3") (pintype "passive"))
      (node (ref "MOT1") (pin "1") (pinfunction "S_1") (pintype "passive"))
    )
    (net (code "65") (name "Net-(MOT1B-S)") (class "Default")
      (node (ref "FL2") (pin "3") (pinfunction "3_3") (pintype "passive"))
      (node (ref "MOT1") (pin "2") (pinfunction "S_2") (pintype "passive"))
    )
    (net (code "66") (name "Net-(MOT2A-S)") (class "Default")
      (node (ref "FL4") (pin "3") (pinfunction "3_3") (pintype "passive"))
      (node (ref "MOT2") (pin "1") (pinfunction "S_1") (pintype "passive"))
    )
    (net (code "67") (name "Net-(MOT2B-S)") (class "Default")
      (node (ref "FL3") (pin "3") (pinfunction "3_3") (pintype "passive"))
      (node (ref "MOT2") (pin "2") (pinfunction "S_2") (pintype "passive"))
    )
    (net (code "68") (name "Net-(MOT3A-S)") (class "Default")
      (node (ref "FL6") (pin "3") (pinfunction "3_3") (pintype "passive"))
      (node (ref "MOT3") (pin "1") (pinfunction "S_1") (pintype "passive"))
    )
    (net (code "69") (name "Net-(MOT3B-S)") (class "Default")
      (node (ref "FL5") (pin "3") (pinfunction "3_3") (pintype "passive"))
      (node (ref "MOT3") (pin "2") (pinfunction "S_2") (pintype "passive"))
    )
    (net (code "70") (name "Net-(MOT4A-S)") (class "Default")
      (node (ref "FL8") (pin "3") (pinfunction "3_3") (pintype "passive"))
      (node (ref "MOT4") (pin "1") (pinfunction "S_1") (pintype "passive"))
    )
    (net (code "71") (name "Net-(MOT4B-S)") (class "Default")
      (node (ref "FL7") (pin "3") (pinfunction "3_3") (pintype "passive"))
      (node (ref "MOT4") (pin "2") (pinfunction "S_2") (pintype "passive"))
    )
    (net (code "72") (name "Net-(MOT5A-S)") (class "Default")
      (node (ref "FL10") (pin "3") (pinfunction "3_3") (pintype "passive"))
      (node (ref "MOT5") (pin "1") (pinfunction "S_1") (pintype "passive"))
    )
    (net (code "73") (name "Net-(MOT5B-S)") (class "Default")
      (node (ref "FL9") (pin "3") (pinfunction "3_3") (pintype "passive"))
      (node (ref "MOT5") (pin "2") (pinfunction "S_2") (pintype "passive"))
    )
    (net (code "74") (name "Net-(MOT6A-S)") (class "Default")
      (node (ref "FL12") (pin "3") (pinfunction "3_3") (pintype "passive"))
      (node (ref "MOT6") (pin "1") (pinfunction "S_1") (pintype "passive"))
    )
    (net (code "75") (name "Net-(MOT6B-S)") (class "Default")
      (node (ref "FL11") (pin "3") (pinfunction "3_3") (pintype "passive"))
      (node (ref "MOT6") (pin "2") (pinfunction "S_2") (pintype "passive"))
    )
    (net (code "76") (name "Net-(OV7670-PadXCLK)") (class "Default")
      (node (ref "OV7670") (pin "XCLK") (pinfunction "XCLK_XCLK") (pintype "bidirectional"))
      (node (ref "R22") (pin "2") (pinfunction "2_2") (pintype "passive"))
      (node (ref "R23") (pin "1") (pinfunction "1_1") (pintype "passive"))
    )
    (net (code "77") (name "Net-(R1-Pad2)") (class "Default")
      (node (ref "R1") (pin "2") (pinfunction "2_2") (pintype "passive"))
      (node (ref "R2") (pin "2") (pinfunction "2_2") (pintype "passive"))
      (node (ref "R3") (pin "2") (pinfunction "2_2") (pintype "passive"))
    )
    (net (code "78") (name "Net-(R3-Pad1)") (class "Default")
      (node (ref "R3") (pin "1") (pinfunction "1_1") (pintype "passive"))
      (node (ref "R4") (pin "2") (pinfunction "2_2") (pintype "passive"))
      (node (ref "R5") (pin "2") (pinfunction "2_2") (pintype "passive"))
    )
    (net (code "79") (name "Net-(R5-Pad1)") (class "Default")
      (node (ref "R5") (pin "1") (pinfunction "1_1") (pintype "passive"))
      (node (ref "R6") (pin "2") (pinfunction "2_2") (pintype "passive"))
      (node (ref "R7") (pin "2") (pinfunction "2_2") (pintype "passive"))
    )
    (net (code "80") (name "Net-(R7-Pad1)") (class "Default")
      (node (ref "R7") (pin "1") (pinfunction "1_1") (pintype "passive"))
      (node (ref "R8") (pin "2") (pinfunction "2_2") (pintype "passive"))
      (node (ref "R9") (pin "2") (pinfunction "2_2") (pintype "passive"))
    )
    (net (code "81") (name "Net-(R10-Pad2)") (class "Default")
      (node (ref "R10") (pin "2") (pinfunction "2_2") (pintype "passive"))
      (node (ref "R11") (pin "2") (pinfunction "2_2") (pintype "passive"))
      (node (ref "R9") (pin "1") (pinfunction "1_1") (pintype "passive"))
    )
    (net (code "82") (name "Net-(R11-Pad1)") (class "Default")
      (node (ref "R11") (pin "1") (pinfunction "1_1") (pintype "passive"))
      (node (ref "R12") (pin "2") (pinfunction "2_2") (pintype "passive"))
      (node (ref "R13") (pin "2") (pinfunction "2_2") (pintype "passive"))
    )
    (net (code "83") (name "Net-(R13-Pad1)") (class "Default")
      (node (ref "R13") (pin "1") (pinfunction "1_1") (pintype "passive"))
      (node (ref "R14") (pin "2") (pinfunction "2_2") (pintype "passive"))
      (node (ref "R15") (pin "2") (pinfunction "2_2") (pintype "passive"))
    )
    (net (code "84") (name "OV_D0") (class "Default")
      (node (ref "ARDUINO-MEGA1") (pin "37") (pinfunction "37_37") (pintype "bidirectional"))
      (node (ref "OV7670") (pin "D0") (pinfunction "D0_D0") (pintype "bidirectional"))
    )
    (net (code "85") (name "OV_D1") (class "Default")
      (node (ref "ARDUINO-MEGA1") (pin "36") (pinfunction "36_36") (pintype "bidirectional"))
      (node (ref "OV7670") (pin "D1") (pinfunction "D1_D1") (pintype "bidirectional"))
    )
    (net (code "86") (name "OV_D2") (class "Default")
      (node (ref "ARDUINO-MEGA1") (pin "35") (pinfunction "35_35") (pintype "bidirectional"))
      (node (ref "OV7670") (pin "D2") (pinfunction "D2_D2") (pintype "bidirectional"))
    )
    (net (code "87") (name "OV_D3") (class "Default")
      (node (ref "ARDUINO-MEGA1") (pin "34") (pinfunction "34_34") (pintype "bidirectional"))
      (node (ref "OV7670") (pin "D3") (pinfunction "D3_D3") (pintype "bidirectional"))
    )
    (net (code "88") (name "OV_D4") (class "Default")
      (node (ref "ARDUINO-MEGA1") (pin "33") (pinfunction "33_33") (pintype "bidirectional"))
      (node (ref "OV7670") (pin "D4") (pinfunction "D4_D4") (pintype "bidirectional"))
    )
    (net (code "89") (name "OV_D5") (class "Default")
      (node (ref "ARDUINO-MEGA1") (pin "32") (pinfunction "32_32") (pintype "bidirectional"))
      (node (ref "OV7670") (pin "D5") (pinfunction "D5_D5") (pintype "bidirectional"))
    )
    (net (code "90") (name "OV_D6") (class "Default")
      (node (ref "ARDUINO-MEGA1") (pin "31") (pinfunction "31_31") (pintype "bidirectional"))
      (node (ref "OV7670") (pin "D6") (pinfunction "D6_D6") (pintype "bidirectional"))
    )
    (net (code "91") (name "OV_D7") (class "Default")
      (node (ref "ARDUINO-MEGA1") (pin "30") (pinfunction "30_30") (pintype "bidirectional"))
      (node (ref "OV7670") (pin "D7") (pinfunction "D7_D7") (pintype "bidirectional"))
    )
    (net (code "92") (name "PCLK") (class "Default")
      (node (ref "ARDUINO-MEGA1") (pin "7") (pinfunction "7_7") (pintype "bidirectional"))
      (node (ref "OV7670") (pin "PCLK") (pinfunction "PCLK_PCLK") (pintype "bidirectional"))
    )
    (net (code "93") (name "RX2") (class "Default")
      (node (ref "ARDUINO-MEGA1") (pin "RX2-17") (pinfunction "RX2-17_RX2-17") (pintype "bidirectional"))
      (node (ref "ESP-01S") (pin "2") (pinfunction "2_2") (pintype "passive"))
    )
    (net (code "94") (name "SCL") (class "Default")
      (node (ref "ARDUINO-MEGA1") (pin "SCL-21") (pinfunction "SCL-21_SCL-21") (pintype "bidirectional"))
      (node (ref "OV7670") (pin "SCL") (pinfunction "SCL_SCL") (pintype "bidirectional"))
      (node (ref "R20") (pin "1") (pinfunction "1_1") (pintype "passive"))
    )
    (net (code "95") (name "SDA") (class "Default")
      (node (ref "ARDUINO-MEGA1") (pin "SDA-20") (pinfunction "SDA-20_SDA-20") (pintype "bidirectional"))
      (node (ref "OV7670") (pin "SDA") (pinfunction "SDA_SDA") (pintype "bidirectional"))
      (node (ref "R21") (pin "1") (pinfunction "1_1") (pintype "passive"))
    )
    (net (code "96") (name "SDCARD-CS") (class "Default")
      (node (ref "ARDUINO-MEGA1") (pin "53") (pinfunction "53_53") (pintype "bidirectional"))
      (node (ref "SDCARD") (pin "1") (pinfunction "1_1") (pintype "passive"))
    )
    (net (code "97") (name "SDCARD-MISO") (class "Default")
      (node (ref "ARDUINO-MEGA1") (pin "50") (pinfunction "50_50") (pintype "bidirectional"))
      (node (ref "SDCARD") (pin "4") (pinfunction "1_4") (pintype "passive"))
    )
    (net (code "98") (name "SDCARD-MOSI") (class "Default")
      (node (ref "ARDUINO-MEGA1") (pin "51") (pinfunction "51_51") (pintype "bidirectional"))
      (node (ref "SDCARD") (pin "3") (pinfunction "1_3") (pintype "passive"))
    )
    (net (code "99") (name "SDCARD-SCK") (class "Default")
      (node (ref "ARDUINO-MEGA1") (pin "52") (pinfunction "52_52") (pintype "bidirectional"))
      (node (ref "SDCARD") (pin "2") (pinfunction "1_2") (pintype "passive"))
    )
    (net (code "100") (name "SENS0") (class "Default")
      (node (ref "ARDUINO-MEGA1") (pin "A0") (pinfunction "A0_A0") (pintype "bidirectional"))
      (node (ref "R30") (pin "2") (pinfunction "2_2") (pintype "passive"))
      (node (ref "S1") (pin "2") (pinfunction "1_2") (pintype "passive"))
    )
    (net (code "101") (name "SENS1") (class "Default")
      (node (ref "ARDUINO-MEGA1") (pin "A1") (pinfunction "A1_A1") (pintype "bidirectional"))
      (node (ref "R31") (pin "2") (pinfunction "2_2") (pintype "passive"))
      (node (ref "S1") (pin "3") (pinfunction "1_3") (pintype "passive"))
    )
    (net (code "102") (name "SENS2") (class "Default")
      (node (ref "ARDUINO-MEGA1") (pin "A2") (pinfunction "A2_A2") (pintype "bidirectional"))
      (node (ref "R33") (pin "2") (pinfunction "2_2") (pintype "passive"))
      (node (ref "S2") (pin "2") (pinfunction "1_2") (pintype "passive"))
    )
    (net (code "103") (name "SENS3") (class "Default")
      (node (ref "ARDUINO-MEGA1") (pin "A3") (pinfunction "A3_A3") (pintype "bidirectional"))
      (node (ref "R34") (pin "2") (pinfunction "2_2") (pintype "passive"))
      (node (ref "S2") (pin "3") (pinfunction "1_3") (pintype "passive"))
    )
    (net (code "104") (name "SENS4") (class "Default")
      (node (ref "ARDUINO-MEGA1") (pin "A4") (pinfunction "A4_A4") (pintype "bidirectional"))
      (node (ref "R36") (pin "2") (pinfunction "2_2") (pintype "passive"))
      (node (ref "S3") (pin "2") (pinfunction "1_2") (pintype "passive"))
    )
    (net (code "105") (name "SENS5") (class "Default")
      (node (ref "ARDUINO-MEGA1") (pin "A5") (pinfunction "A5_A5") (pintype "bidirectional"))
      (node (ref "R37") (pin "2") (pinfunction "2_2") (pintype "passive"))
      (node (ref "S3") (pin "3") (pinfunction "1_3") (pintype "passive"))
    )
    (net (code "106") (name "SENS6") (class "Default")
      (node (ref "ARDUINO-MEGA1") (pin "A6") (pinfunction "A6_A6") (pintype "bidirectional"))
      (node (ref "R39") (pin "2") (pinfunction "2_2") (pintype "passive"))
      (node (ref "S4") (pin "2") (pinfunction "1_2") (pintype "passive"))
    )
    (net (code "107") (name "SENS7") (class "Default")
      (node (ref "ARDUINO-MEGA1") (pin "A7") (pinfunction "A7_A7") (pintype "bidirectional"))
      (node (ref "R40") (pin "2") (pinfunction "2_2") (pintype "passive"))
      (node (ref "S4") (pin "3") (pinfunction "1_3") (pintype "passive"))
    )
    (net (code "108") (name "SENS8") (class "Default")
      (node (ref "ARDUINO-MEGA1") (pin "A8") (pinfunction "A8_A8") (pintype "bidirectional"))
      (node (ref "R42") (pin "2") (pinfunction "2_2") (pintype "passive"))
      (node (ref "S5") (pin "2") (pinfunction "1_2") (pintype "passive"))
    )
    (net (code "109") (name "SENS9") (class "Default")
      (node (ref "ARDUINO-MEGA1") (pin "A9") (pinfunction "A9_A9") (pintype "bidirectional"))
      (node (ref "R43") (pin "2") (pinfunction "2_2") (pintype "passive"))
      (node (ref "S5") (pin "3") (pinfunction "1_3") (pintype "passive"))
    )
    (net (code "110") (name "SENS10") (class "Default")
      (node (ref "ARDUINO-MEGA1") (pin "A10") (pinfunction "A10_A10") (pintype "bidirectional"))
      (node (ref "R45") (pin "2") (pinfunction "2_2") (pintype "passive"))
      (node (ref "S6") (pin "2") (pinfunction "1_2") (pintype "passive"))
    )
    (net (code "111") (name "SENS11") (class "Default")
      (node (ref "ARDUINO-MEGA1") (pin "A11") (pinfunction "A11_A11") (pintype "bidirectional"))
      (node (ref "R46") (pin "2") (pinfunction "2_2") (pintype "passive"))
      (node (ref "S6") (pin "3") (pinfunction "1_3") (pintype "passive"))
    )
    (net (code "112") (name "SENS12") (class "Default")
      (node (ref "ARDUINO-MEGA1") (pin "A12") (pinfunction "A12_A12") (pintype "bidirectional"))
      (node (ref "R48") (pin "2") (pinfunction "2_2") (pintype "passive"))
      (node (ref "S7") (pin "2") (pinfunction "1_2") (pintype "passive"))
    )
    (net (code "113") (name "SENS13") (class "Default")
      (node (ref "ARDUINO-MEGA1") (pin "A13") (pinfunction "A13_A13") (pintype "bidirectional"))
      (node (ref "R49") (pin "2") (pinfunction "2_2") (pintype "passive"))
      (node (ref "S7") (pin "3") (pinfunction "1_3") (pintype "passive"))
    )
    (net (code "114") (name "SENS14") (class "Default")
      (node (ref "ARDUINO-MEGA1") (pin "A14") (pinfunction "A14_A14") (pintype "bidirectional"))
      (node (ref "R51") (pin "2") (pinfunction "2_2") (pintype "passive"))
      (node (ref "S8") (pin "2") (pinfunction "1_2") (pintype "passive"))
    )
    (net (code "115") (name "SENS15") (class "Default")
      (node (ref "ARDUINO-MEGA1") (pin "A15") (pinfunction "A15_A15") (pintype "bidirectional"))
      (node (ref "R52") (pin "2") (pinfunction "2_2") (pintype "passive"))
      (node (ref "S8") (pin "3") (pinfunction "1_3") (pintype "passive"))
    )
    (net (code "116") (name "TX2") (class "Default")
      (node (ref "ARDUINO-MEGA1") (pin "TX2-16") (pinfunction "TX2-16_TX2-16") (pintype "bidirectional"))
      (node (ref "R25") (pin "1") (pinfunction "1_1") (pintype "passive"))
    )
    (net (code "117") (name "VSYNC") (class "Default")
      (node (ref "ARDUINO-MEGA1") (pin "9") (pinfunction "9_9") (pintype "bidirectional"))
      (node (ref "OV7670") (pin "VSYNC") (pinfunction "VSYNC_VSYNC") (pintype "bidirectional"))
    )
    (net (code "118") (name "XCLK") (class "Default")
      (node (ref "ARDUINO-MEGA1") (pin "6") (pinfunction "6_6") (pintype "bidirectional"))
      (node (ref "R23") (pin "2") (pinfunction "2_2") (pintype "passive"))
    )
    (net (code "119") (name "unconnected-(ARDUINO-MEGA1-Pad5V_2)") (class "Default")
      (node (ref "ARDUINO-MEGA1") (pin "5V_2") (pinfunction "5V_2_5V_2") (pintype "bidirectional"))
    )
    (net (code "120") (name "unconnected-(ARDUINO-MEGA1-Pad5V_3)") (class "Default")
      (node (ref "ARDUINO-MEGA1") (pin "5V_3") (pinfunction "5V_3_5V_3") (pintype "bidirectional"))
    )
    (net (code "121") (name "unconnected-(ARDUINO-MEGA1-Pad23)") (class "Default")
      (node (ref "ARDUINO-MEGA1") (pin "23") (pinfunction "23_23") (pintype "bidirectional"))
    )
    (net (code "122") (name "unconnected-(ARDUINO-MEGA1-Pad25)") (class "Default")
      (node (ref "ARDUINO-MEGA1") (pin "25") (pinfunction "25_25") (pintype "bidirectional"))
    )
    (net (code "123") (name "unconnected-(ARDUINO-MEGA1-Pad27)") (class "Default")
      (node (ref "ARDUINO-MEGA1") (pin "27") (pinfunction "27_27") (pintype "bidirectional"))
    )
    (net (code "124") (name "unconnected-(ARDUINO-MEGA1-Pad29)") (class "Default")
      (node (ref "ARDUINO-MEGA1") (pin "29") (pinfunction "29_29") (pintype "bidirectional"))
    )
    (net (code "125") (name "unconnected-(ARDUINO-MEGA1-Pad38)") (class "Default")
      (node (ref "ARDUINO-MEGA1") (pin "38") (pinfunction "38_38") (pintype "bidirectional"))
    )
    (net (code "126") (name "unconnected-(ARDUINO-MEGA1-Pad39)") (class "Default")
      (node (ref "ARDUINO-MEGA1") (pin "39") (pinfunction "39_39") (pintype "bidirectional"))
    )
    (net (code "127") (name "unconnected-(ARDUINO-MEGA1-Pad41)") (class "Default")
      (node (ref "ARDUINO-MEGA1") (pin "41") (pinfunction "41_41") (pintype "bidirectional"))
    )
    (net (code "128") (name "unconnected-(ARDUINO-MEGA1-PadAREF)") (class "Default")
      (node (ref "ARDUINO-MEGA1") (pin "AREF") (pinfunction "AREF_AREF") (pintype "bidirectional"))
    )
    (net (code "129") (name "unconnected-(ARDUINO-MEGA1-PadIOREF)") (class "Default")
      (node (ref "ARDUINO-MEGA1") (pin "IOREF") (pinfunction "IOREF_IOREF") (pintype "bidirectional"))
    )
    (net (code "130") (name "unconnected-(ARDUINO-MEGA1-PadN.C.)") (class "Default")
      (node (ref "ARDUINO-MEGA1") (pin "N.C.") (pinfunction "N.C._N.C.") (pintype "bidirectional"))
    )
    (net (code "131") (name "unconnected-(ARDUINO-MEGA1-PadRESET)") (class "Default")
      (node (ref "ARDUINO-MEGA1") (pin "RESET") (pinfunction "RESET_RESET") (pintype "bidirectional"))
    )
    (net (code "132") (name "unconnected-(ARDUINO-MEGA1-PadRX0-0)") (class "Default")
      (node (ref "ARDUINO-MEGA1") (pin "RX0-0") (pinfunction "RX0-0_RX0-0") (pintype "bidirectional"))
    )
    (net (code "133") (name "unconnected-(ARDUINO-MEGA1-PadRX3-15)") (class "Default")
      (node (ref "ARDUINO-MEGA1") (pin "RX3-15") (pinfunction "RX3-15_RX3-15") (pintype "bidirectional"))
    )
    (net (code "134") (name "unconnected-(ARDUINO-MEGA1-PadSCL)") (class "Default")
      (node (ref "ARDUINO-MEGA1") (pin "SCL") (pinfunction "SCL_SCL") (pintype "bidirectional"))
    )
    (net (code "135") (name "unconnected-(ARDUINO-MEGA1-PadSDA)") (class "Default")
      (node (ref "ARDUINO-MEGA1") (pin "SDA") (pinfunction "SDA_SDA") (pintype "bidirectional"))
    )
    (net (code "136") (name "unconnected-(ARDUINO-MEGA1-PadTX0-1)") (class "Default")
      (node (ref "ARDUINO-MEGA1") (pin "TX0-1") (pinfunction "TX0-1_TX0-1") (pintype "bidirectional"))
    )
    (net (code "137") (name "unconnected-(ARDUINO-MEGA1-PadTX3-14)") (class "Default")
      (node (ref "ARDUINO-MEGA1") (pin "TX3-14") (pinfunction "TX3-14_TX3-14") (pintype "bidirectional"))
    )
    (net (code "138") (name "unconnected-(ARDUINO-MEGA1-PadVIN)") (class "Default")
      (node (ref "ARDUINO-MEGA1") (pin "VIN") (pinfunction "VIN_VIN") (pintype "bidirectional"))
    )
    (net (code "139") (name "unconnected-(ESP-01S-Pad3)") (class "Default")
      (node (ref "ESP-01S") (pin "3") (pinfunction "3_3") (pintype "passive"))
    )
    (net (code "140") (name "unconnected-(ESP-01S-Pad5)") (class "Default")
      (node (ref "ESP-01S") (pin "5") (pinfunction "5_5") (pintype "passive"))
    )
    (net (code "141") (name "{slash}DAC_SD") (class "Default")
      (node (ref "ARDUINO-MEGA1") (pin "40") (pinfunction "40_40") (pintype "bidirectional"))
      (node (ref "IC1") (pin "1") (pinfunction "/SHUTDOWN_1") (pintype "bidirectional"))
      (node (ref "R17") (pin "2") (pinfunction "2_2") (pintype "passive"))
    )
    (net (code "142") (name "{slash}ESP_RST") (class "Default")
      (node (ref "ARDUINO-MEGA1") (pin "RX1-19") (pinfunction "RX1-19_RX1-19") (pintype "bidirectional"))
      (node (ref "R27") (pin "2") (pinfunction "2_2") (pintype "passive"))
    )
  )
)
